# SNES_AddOn1Chip.net
KiCad netlist of a schematic drawn in EAGLE
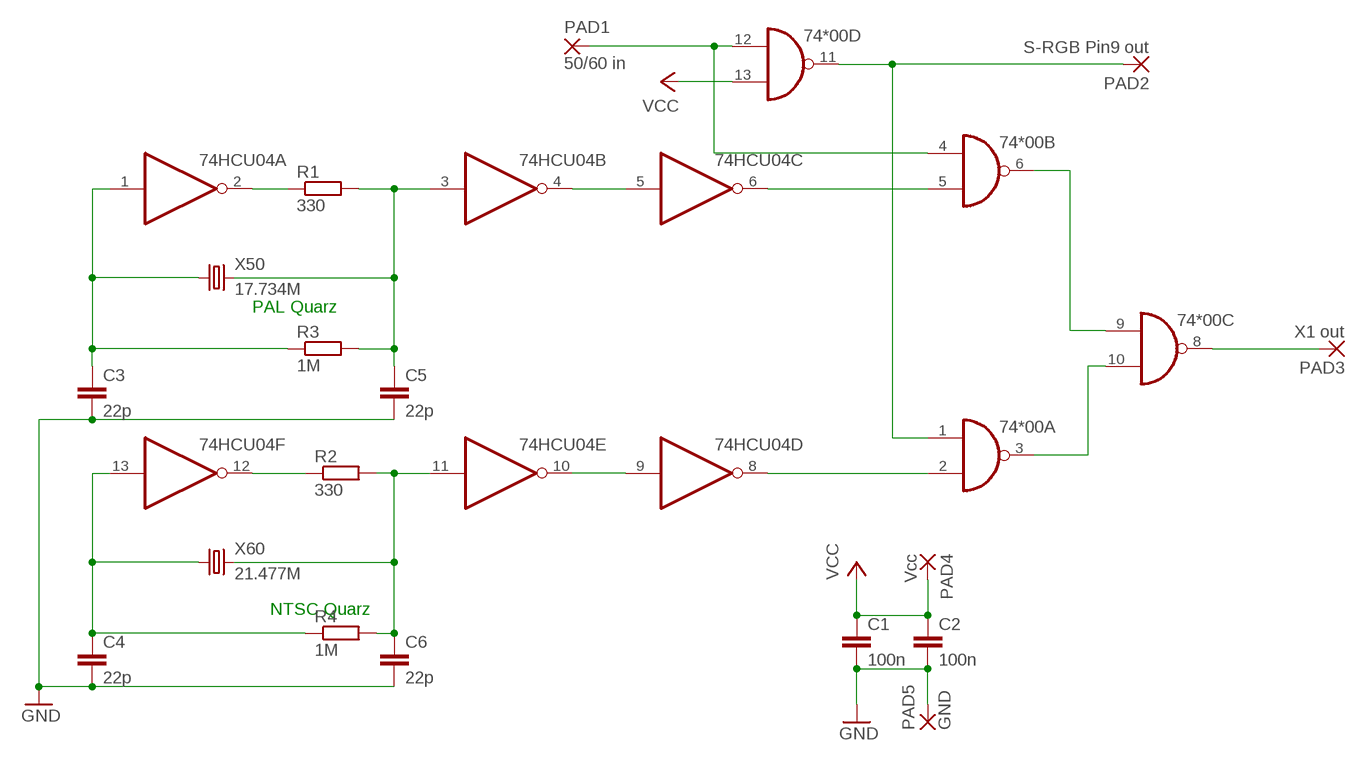
[diagram p0: schematic, sheet 1]

(export (version "E")
  (design (tool "Eeschema 10.0.6"))
  (components
    (comp (ref "74*00")
      (value "7400D")
      (footprint "eagle-import:SO14")
      (libsource (lib "eagle-import") (part "7400D"))
    )
    (comp (ref "74HCU04")
      (value "74HC04D")
      (footprint "eagle-import:SO14")
      (libsource (lib "eagle-import") (part "7404DHC"))
    )
    (comp (ref "C1")
      (value "100n")
      (footprint "eagle-import:Z0805")
      (libsource (lib "eagle-import") (part "C0805"))
    )
    (comp (ref "C2")
      (value "100n")
      (footprint "eagle-import:Z0805")
      (libsource (lib "eagle-import") (part "C0805"))
    )
    (comp (ref "C3")
      (value "22p")
      (footprint "eagle-import:Z0805")
      (libsource (lib "eagle-import") (part "C0805"))
    )
    (comp (ref "C4")
      (value "22p")
      (footprint "eagle-import:Z0805")
      (libsource (lib "eagle-import") (part "C0805"))
    )
    (comp (ref "C5")
      (value "22p")
      (footprint "eagle-import:Z0805")
      (libsource (lib "eagle-import") (part "C0805"))
    )
    (comp (ref "C6")
      (value "22p")
      (footprint "eagle-import:Z0805")
      (libsource (lib "eagle-import") (part "C0805"))
    )
    (comp (ref "PAD1")
      (value "50/60 in")
      (footprint "eagle-import:SMD1,27-2,54")
      (libsource (lib "eagle-import") (part "SMD2"))
    )
    (comp (ref "PAD2")
      (value "S-RGB Pin9 out")
      (footprint "eagle-import:SMD1,27-2,54")
      (libsource (lib "eagle-import") (part "SMD2"))
    )
    (comp (ref "PAD3")
      (value "X1 out")
      (footprint "eagle-import:SMD1,27-2,54")
      (libsource (lib "eagle-import") (part "SMD2"))
    )
    (comp (ref "PAD4")
      (value "Vcc")
      (footprint "eagle-import:SMD2,54-5,08")
      (libsource (lib "eagle-import") (part "SMD5"))
    )
    (comp (ref "PAD5")
      (value "GND")
      (footprint "eagle-import:SMD2,54-5,08")
      (libsource (lib "eagle-import") (part "SMD5"))
    )
    (comp (ref "R1")
      (value "330")
      (footprint "eagle-import:Z0805")
      (libsource (lib "eagle-import") (part "R0805"))
    )
    (comp (ref "R2")
      (value "330")
      (footprint "eagle-import:Z0805")
      (libsource (lib "eagle-import") (part "R0805"))
    )
    (comp (ref "R3")
      (value "1M")
      (footprint "eagle-import:Z0805")
      (libsource (lib "eagle-import") (part "R0805"))
    )
    (comp (ref "R4")
      (value "1M")
      (footprint "eagle-import:Z0805")
      (libsource (lib "eagle-import") (part "R0805"))
    )
    (comp (ref "X50")
      (value "17.734M")
      (footprint "eagle-import:HC49_S")
      (libsource (lib "eagle-import") (part "CRYSTALHC49S"))
    )
    (comp (ref "X60")
      (value "21.477M")
      (footprint "eagle-import:HC49_S")
      (libsource (lib "eagle-import") (part "CRYSTALHC49S"))
    )
  )
  (nets
    (net (code "1") (name "GND") (class "Default")
      (node (ref "C1") (pin "2") (pinfunction "2_2") (pintype "passive"))
      (node (ref "C2") (pin "2") (pinfunction "2_2") (pintype "passive"))
      (node (ref "C3") (pin "2") (pinfunction "2_2") (pintype "passive"))
      (node (ref "C4") (pin "2") (pinfunction "2_2") (pintype "passive"))
      (node (ref "C5") (pin "2") (pinfunction "2_2") (pintype "passive"))
      (node (ref "C6") (pin "2") (pinfunction "2_2") (pintype "passive"))
      (node (ref "PAD5") (pin "1") (pinfunction "P_1") (pintype "passive"))
    )
    (net (code "2") (name "Net-(74*00A-I0)") (class "Default")
      (node (ref "74*00") (pin "1") (pinfunction "I0_1") (pintype "input"))
      (node (ref "74*00") (pin "11") (pinfunction "O_11") (pintype "output"))
      (node (ref "PAD2") (pin "1") (pinfunction "P_1") (pintype "passive"))
    )
    (net (code "3") (name "Net-(74*00A-I1)") (class "Default")
      (node (ref "74*00") (pin "2") (pinfunction "I1_2") (pintype "input"))
      (node (ref "74HCU04") (pin "8") (pinfunction "O_8") (pintype "output"))
    )
    (net (code "4") (name "Net-(74*00A-O)") (class "Default")
      (node (ref "74*00") (pin "10") (pinfunction "I1_10") (pintype "input"))
      (node (ref "74*00") (pin "3") (pinfunction "O_3") (pintype "output"))
    )
    (net (code "5") (name "Net-(74*00B-I0)") (class "Default")
      (node (ref "74*00") (pin "12") (pinfunction "I0_12") (pintype "input"))
      (node (ref "74*00") (pin "4") (pinfunction "I0_4") (pintype "input"))
      (node (ref "PAD1") (pin "1") (pinfunction "P_1") (pintype "passive"))
    )
    (net (code "6") (name "Net-(74*00B-I1)") (class "Default")
      (node (ref "74*00") (pin "5") (pinfunction "I1_5") (pintype "input"))
      (node (ref "74HCU04") (pin "6") (pinfunction "O_6") (pintype "output"))
    )
    (net (code "7") (name "Net-(74*00B-O)") (class "Default")
      (node (ref "74*00") (pin "6") (pinfunction "O_6") (pintype "output"))
      (node (ref "74*00") (pin "9") (pinfunction "I0_9") (pintype "input"))
    )
    (net (code "8") (name "Net-(74*00C-O)") (class "Default")
      (node (ref "74*00") (pin "8") (pinfunction "O_8") (pintype "output"))
      (node (ref "PAD3") (pin "1") (pinfunction "P_1") (pintype "passive"))
    )
    (net (code "9") (name "Net-(74HCU04A-I)") (class "Default")
      (node (ref "74HCU04") (pin "1") (pinfunction "I_1") (pintype "input"))
      (node (ref "C3") (pin "1") (pinfunction "1_1") (pintype "passive"))
      (node (ref "R3") (pin "1") (pinfunction "1_1") (pintype "passive"))
      (node (ref "X50") (pin "1") (pinfunction "1_1") (pintype "passive"))
    )
    (net (code "10") (name "Net-(74HCU04A-O)") (class "Default")
      (node (ref "74HCU04") (pin "2") (pinfunction "O_2") (pintype "output"))
      (node (ref "R1") (pin "1") (pinfunction "1_1") (pintype "passive"))
    )
    (net (code "11") (name "Net-(74HCU04B-I)") (class "Default")
      (node (ref "74HCU04") (pin "3") (pinfunction "I_3") (pintype "input"))
      (node (ref "C5") (pin "1") (pinfunction "1_1") (pintype "passive"))
      (node (ref "R1") (pin "2") (pinfunction "2_2") (pintype "passive"))
      (node (ref "R3") (pin "2") (pinfunction "2_2") (pintype "passive"))
      (node (ref "X50") (pin "2") (pinfunction "2_2") (pintype "passive"))
    )
    (net (code "12") (name "Net-(74HCU04B-O)") (class "Default")
      (node (ref "74HCU04") (pin "4") (pinfunction "O_4") (pintype "output"))
      (node (ref "74HCU04") (pin "5") (pinfunction "I_5") (pintype "input"))
    )
    (net (code "13") (name "Net-(74HCU04D-I)") (class "Default")
      (node (ref "74HCU04") (pin "10") (pinfunction "O_10") (pintype "output"))
      (node (ref "74HCU04") (pin "9") (pinfunction "I_9") (pintype "input"))
    )
    (net (code "14") (name "Net-(74HCU04E-I)") (class "Default")
      (node (ref "74HCU04") (pin "11") (pinfunction "I_11") (pintype "input"))
      (node (ref "C6") (pin "1") (pinfunction "1_1") (pintype "passive"))
      (node (ref "R2") (pin "2") (pinfunction "2_2") (pintype "passive"))
      (node (ref "R4") (pin "2") (pinfunction "2_2") (pintype "passive"))
      (node (ref "X60") (pin "2") (pinfunction "2_2") (pintype "passive"))
    )
    (net (code "15") (name "Net-(74HCU04F-I)") (class "Default")
      (node (ref "74HCU04") (pin "13") (pinfunction "I_13") (pintype "input"))
      (node (ref "C4") (pin "1") (pinfunction "1_1") (pintype "passive"))
      (node (ref "R4") (pin "1") (pinfunction "1_1") (pintype "passive"))
      (node (ref "X60") (pin "1") (pinfunction "1_1") (pintype "passive"))
    )
    (net (code "16") (name "Net-(74HCU04F-O)") (class "Default")
      (node (ref "74HCU04") (pin "12") (pinfunction "O_12") (pintype "output"))
      (node (ref "R2") (pin "1") (pinfunction "1_1") (pintype "passive"))
    )
    (net (code "17") (name "VCC") (class "Default")
      (node (ref "74*00") (pin "13") (pinfunction "I1_13") (pintype "input"))
      (node (ref "C1") (pin "1") (pinfunction "1_1") (pintype "passive"))
      (node (ref "C2") (pin "1") (pinfunction "1_1") (pintype "passive"))
      (node (ref "PAD4") (pin "1") (pinfunction "P_1") (pintype "passive"))
    )
  )
)
